# can-rs232.net
KiCad netlist of a schematic drawn in EAGLE
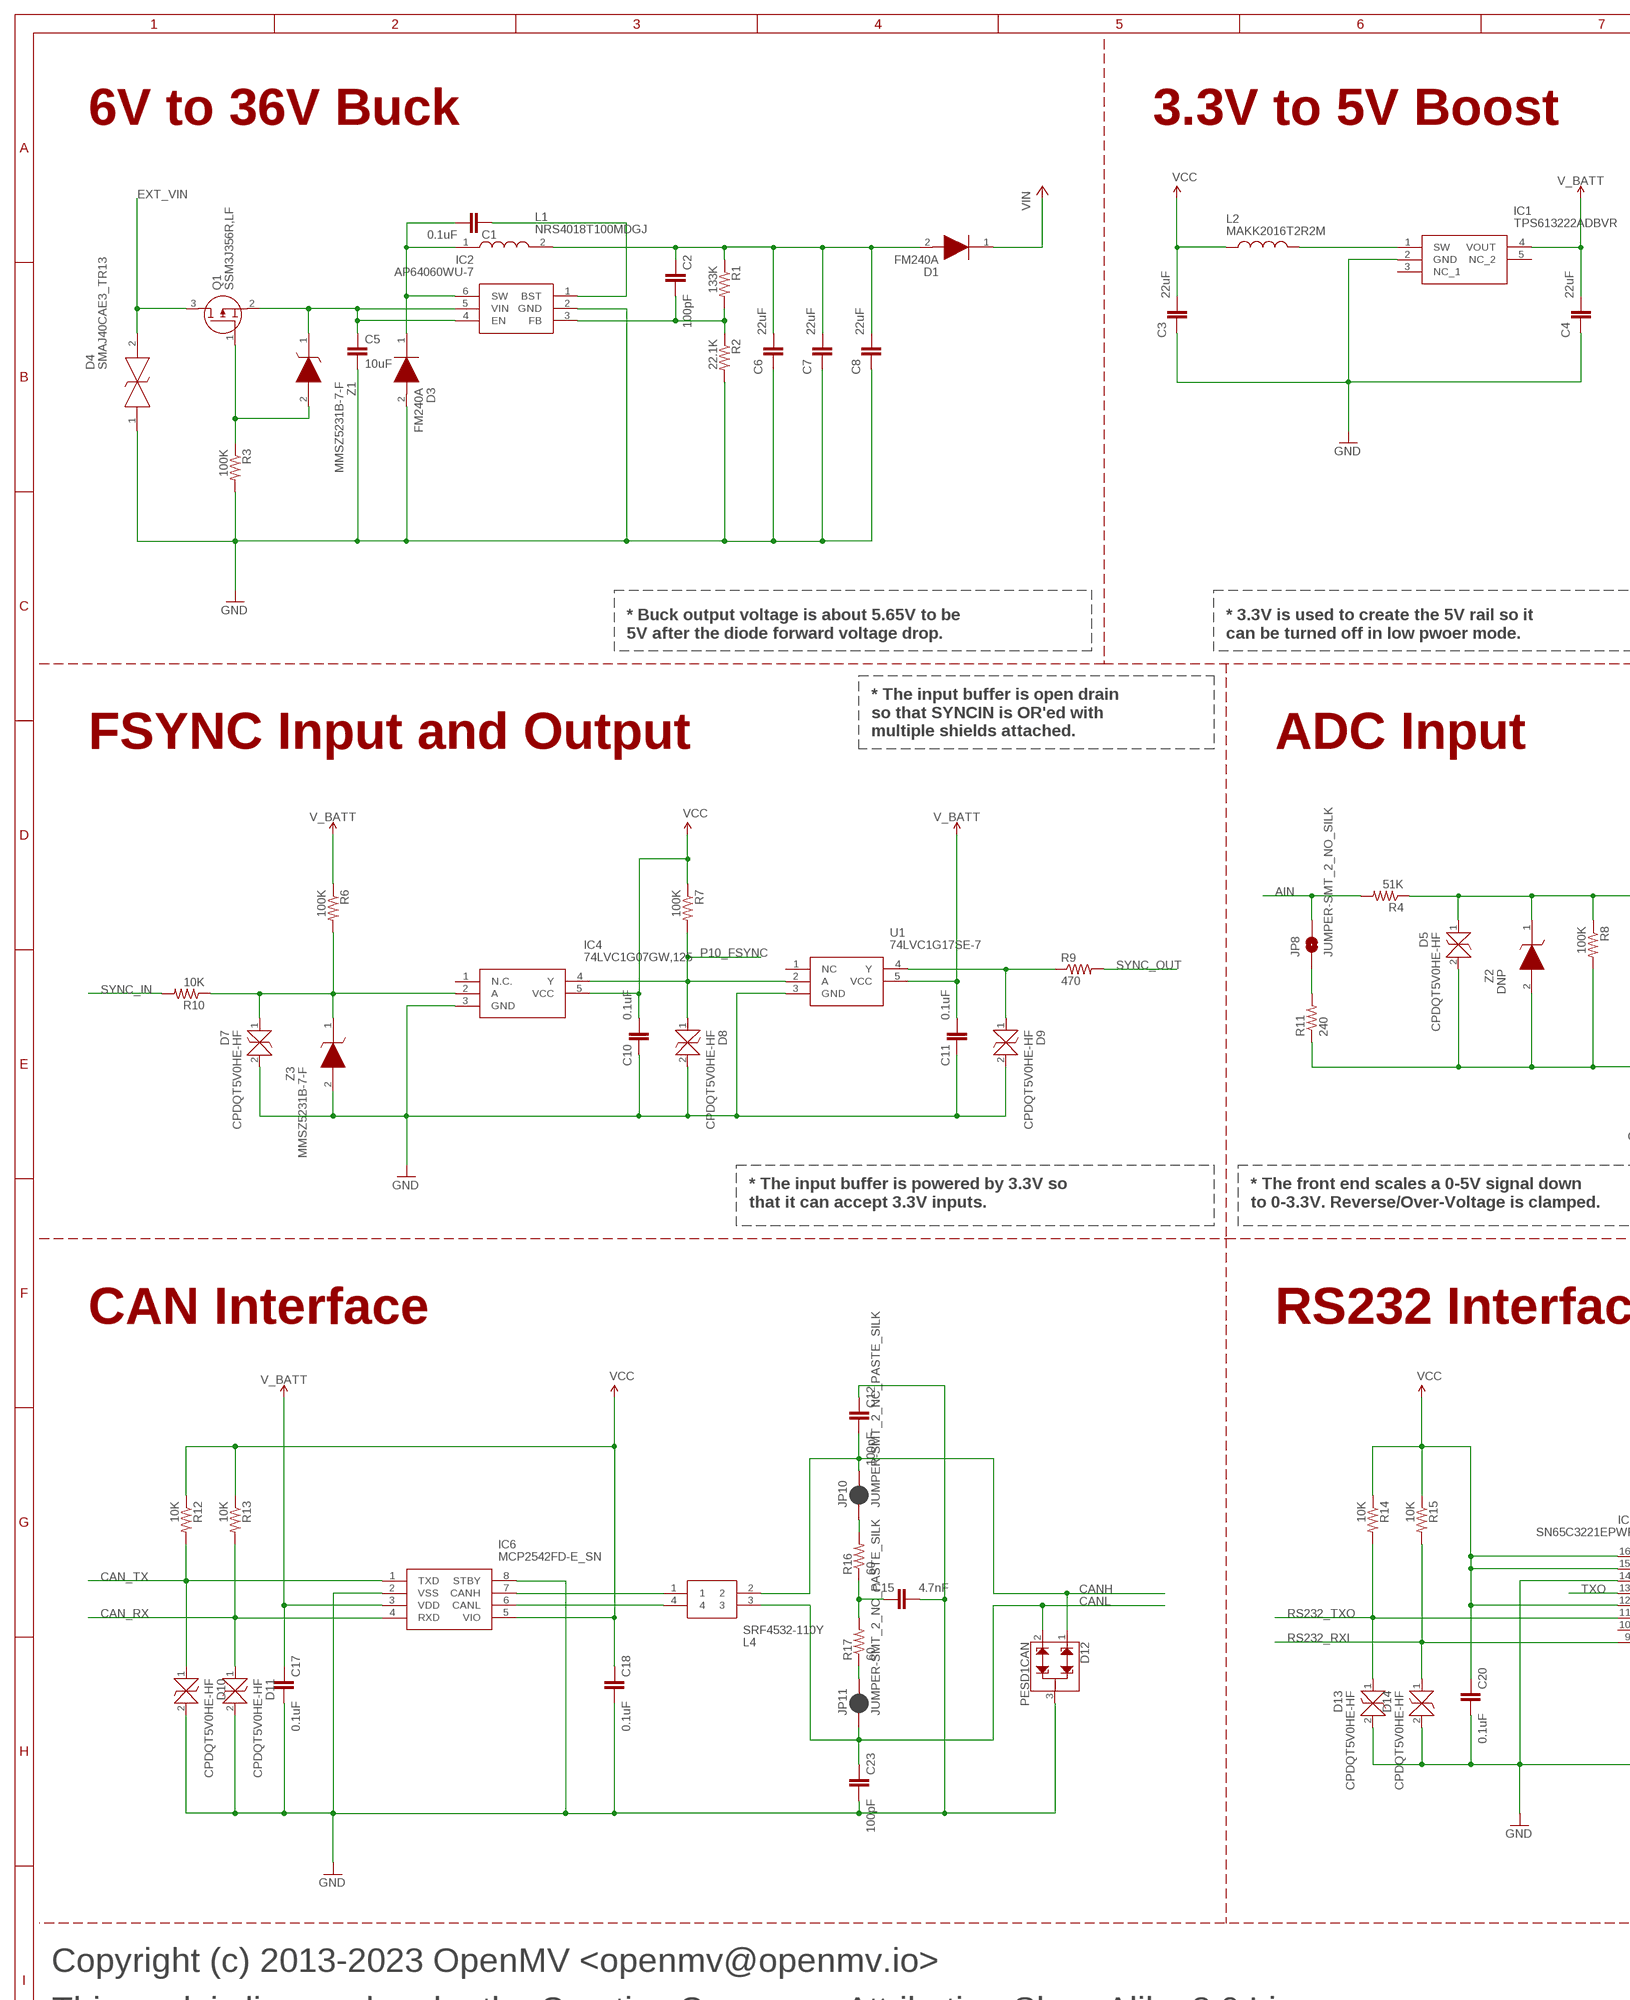
[diagram p0: schematic, sheet 1, part 1 of 2]
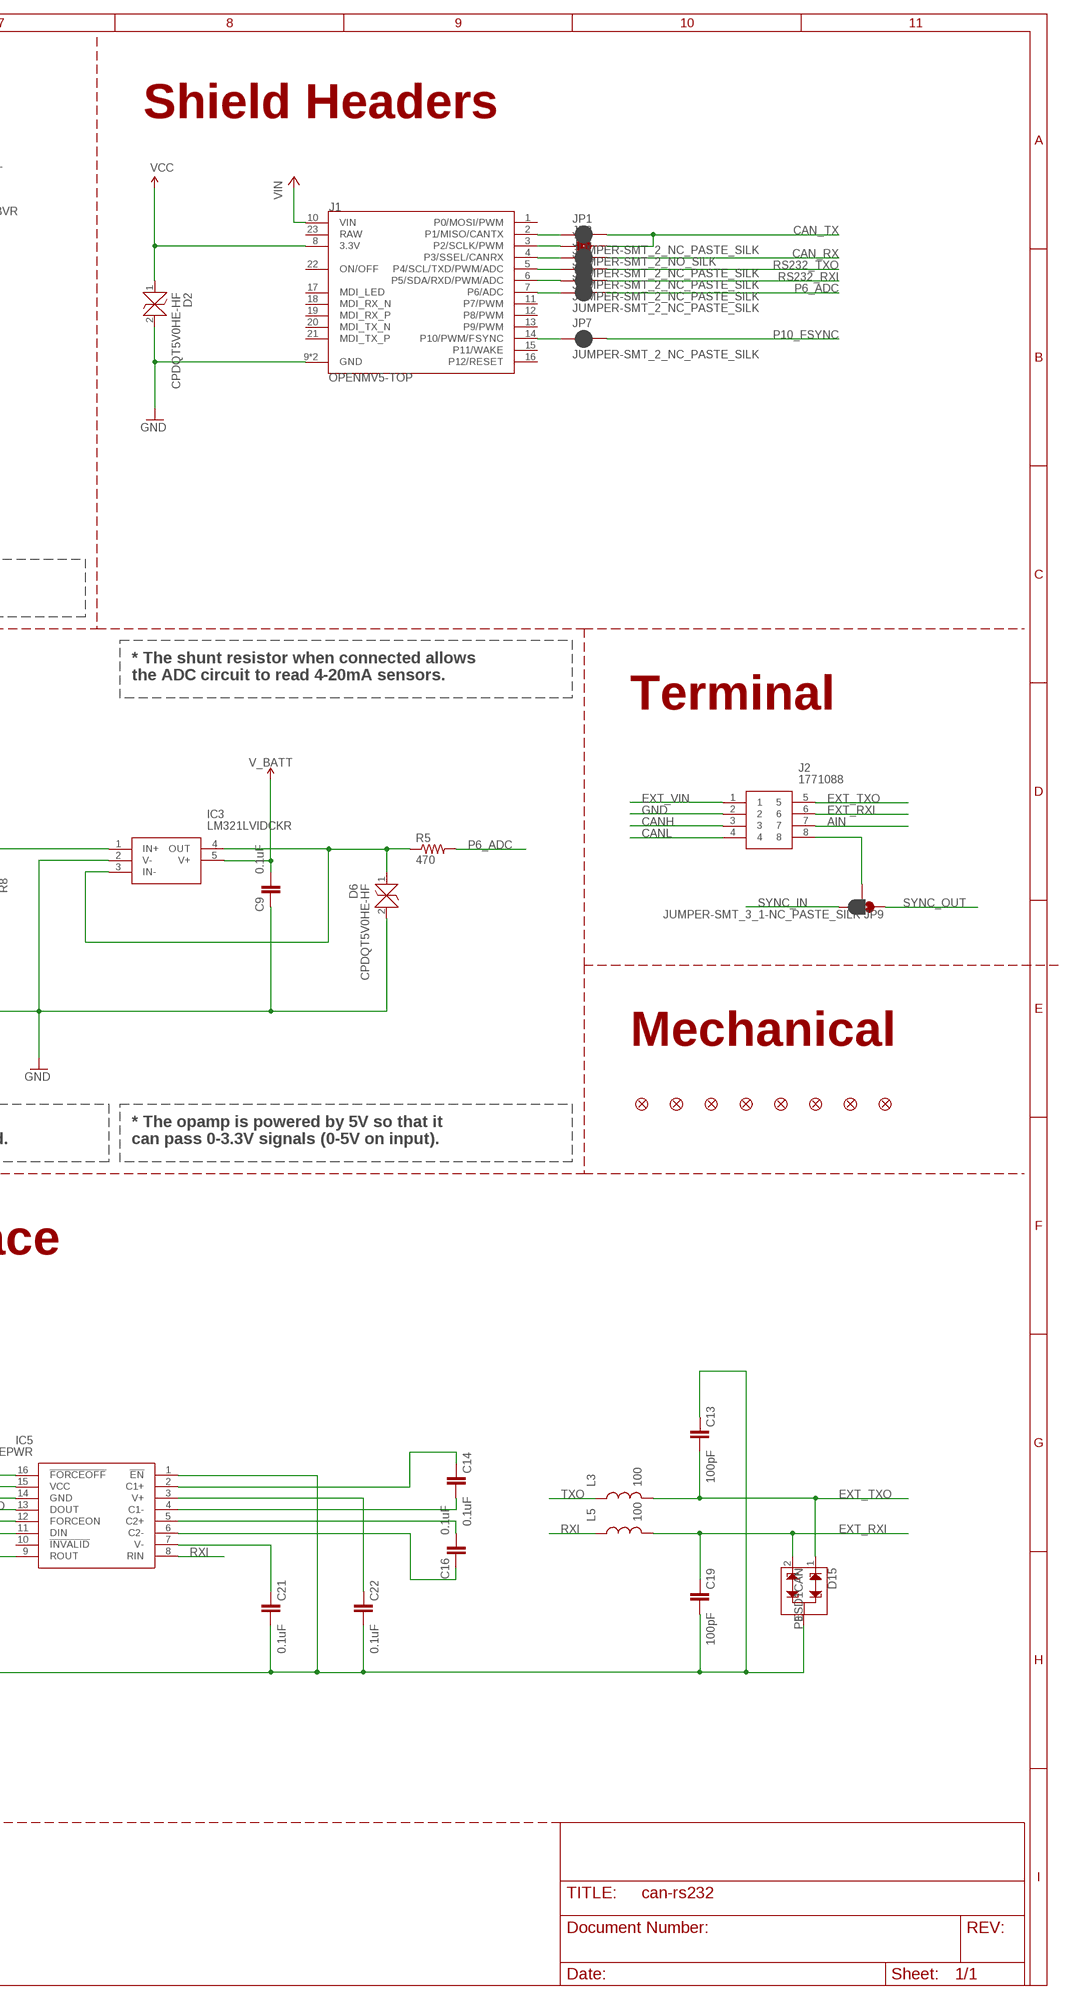
[diagram p1: schematic, sheet 1, part 2 of 2]

(export (version "E")
  (design (tool "Eeschema 10.0.6"))
  (components
    (comp (ref "C1")
      (value "0.1uF")
      (footprint "eagle-import:0402-CAP")
      (fields (field (name "MPN") "GRM155R71H104KE14D"))
      (libsource (lib "eagle-import") (part "CAP0402-CAP"))
    )
    (comp (ref "C2")
      (value "100pF")
      (footprint "eagle-import:0402-CAP")
      (fields (field (name "MPN") "CC0402JRNPO9BN101"))
      (libsource (lib "eagle-import") (part "CAP0402-CAP"))
    )
    (comp (ref "C3")
      (value "22uF")
      (footprint "eagle-import:0805")
      (fields (field (name "MPN") "CL21A226MQQNNNE"))
      (libsource (lib "eagle-import") (part "22UF-0805-6.3V-20%"))
    )
    (comp (ref "C4")
      (value "22uF")
      (footprint "eagle-import:0805")
      (fields (field (name "MPN") "CL21A226MQQNNNE"))
      (libsource (lib "eagle-import") (part "22UF-0805-6.3V-20%"))
    )
    (comp (ref "C5")
      (value "10uF")
      (footprint "eagle-import:C0805")
      (fields (field (name "MPN") "GRM21BR61H106KE43K"))
      (libsource (lib "eagle-import") (part "C-EUC0805"))
    )
    (comp (ref "C6")
      (value "22uF")
      (footprint "eagle-import:0805")
      (fields (field (name "MPN") "CL21A226MQQNNNE"))
      (libsource (lib "eagle-import") (part "22UF-0805-6.3V-20%"))
    )
    (comp (ref "C7")
      (value "22uF")
      (footprint "eagle-import:0805")
      (fields (field (name "MPN") "CL21A226MQQNNNE"))
      (libsource (lib "eagle-import") (part "22UF-0805-6.3V-20%"))
    )
    (comp (ref "C8")
      (value "22uF")
      (footprint "eagle-import:0805")
      (fields (field (name "MPN") "CL21A226MQQNNNE"))
      (libsource (lib "eagle-import") (part "22UF-0805-6.3V-20%"))
    )
    (comp (ref "C9")
      (value "0.1uF")
      (footprint "eagle-import:0402-CAP")
      (fields (field (name "MPN") "GRM155R71H104KE14D"))
      (libsource (lib "eagle-import") (part "CAP0402-CAP"))
    )
    (comp (ref "C10")
      (value "0.1uF")
      (footprint "eagle-import:0402-CAP")
      (fields (field (name "MPN") "GRM155R71H104KE14D"))
      (libsource (lib "eagle-import") (part "CAP0402-CAP"))
    )
    (comp (ref "C11")
      (value "0.1uF")
      (footprint "eagle-import:0402-CAP")
      (fields (field (name "MPN") "GRM155R71H104KE14D"))
      (libsource (lib "eagle-import") (part "CAP0402-CAP"))
    )
    (comp (ref "C12")
      (value "100pF")
      (footprint "eagle-import:0402-CAP")
      (fields (field (name "MPN") "CC0402JRNPO9BN101"))
      (libsource (lib "eagle-import") (part "CAP0402-CAP"))
    )
    (comp (ref "C13")
      (value "100pF")
      (footprint "eagle-import:0402-CAP")
      (fields (field (name "MPN") "CC0402JRNPO9BN101"))
      (libsource (lib "eagle-import") (part "CAP0402-CAP"))
    )
    (comp (ref "C14")
      (value "0.1uF")
      (footprint "eagle-import:0402-CAP")
      (fields (field (name "MPN") "GRM155R71H104KE14D"))
      (libsource (lib "eagle-import") (part "CAP0402-CAP"))
    )
    (comp (ref "C15")
      (value "4.7nF")
      (footprint "eagle-import:0402-CAP")
      (fields (field (name "MPN") "GRM155R71H472JA01D"))
      (libsource (lib "eagle-import") (part "CAP0402-CAP"))
    )
    (comp (ref "C16")
      (value "0.1uF")
      (footprint "eagle-import:0402-CAP")
      (fields (field (name "MPN") "GRM155R71H104KE14D"))
      (libsource (lib "eagle-import") (part "CAP0402-CAP"))
    )
    (comp (ref "C17")
      (value "0.1uF")
      (footprint "eagle-import:0402-CAP")
      (fields (field (name "MPN") "GRM155R71H104KE14D"))
      (libsource (lib "eagle-import") (part "CAP0402-CAP"))
    )
    (comp (ref "C18")
      (value "0.1uF")
      (footprint "eagle-import:0402-CAP")
      (fields (field (name "MPN") "GRM155R71H104KE14D"))
      (libsource (lib "eagle-import") (part "CAP0402-CAP"))
    )
    (comp (ref "C19")
      (value "100pF")
      (footprint "eagle-import:0402-CAP")
      (fields (field (name "MPN") "CC0402JRNPO9BN101"))
      (libsource (lib "eagle-import") (part "CAP0402-CAP"))
    )
    (comp (ref "C20")
      (value "0.1uF")
      (footprint "eagle-import:0402-CAP")
      (fields (field (name "MPN") "GRM155R71H104KE14D"))
      (libsource (lib "eagle-import") (part "CAP0402-CAP"))
    )
    (comp (ref "C21")
      (value "0.1uF")
      (footprint "eagle-import:0402-CAP")
      (fields (field (name "MPN") "GRM155R71H104KE14D"))
      (libsource (lib "eagle-import") (part "CAP0402-CAP"))
    )
    (comp (ref "C22")
      (value "0.1uF")
      (footprint "eagle-import:0402-CAP")
      (fields (field (name "MPN") "GRM155R71H104KE14D"))
      (libsource (lib "eagle-import") (part "CAP0402-CAP"))
    )
    (comp (ref "C23")
      (value "100pF")
      (footprint "eagle-import:0402-CAP")
      (fields (field (name "MPN") "CC0402JRNPO9BN101"))
      (libsource (lib "eagle-import") (part "CAP0402-CAP"))
    )
    (comp (ref "D1")
      (value "FM240A")
      (footprint "eagle-import:DIOM5025X231N")
      (fields (field (name "MOUSER_PART_NUMBER") "583-FM240A"))
      (libsource (lib "eagle-import") (part "FM240A"))
    )
    (comp (ref "D2")
      (value "CPDQT5V0HE-HF")
      (footprint "eagle-import:CPDQT5V0HEHF")
      (libsource (lib "eagle-import") (part "CPDQT5V0HE-HF"))
    )
    (comp (ref "D3")
      (value "FM240A")
      (footprint "eagle-import:DIOM5025X231N")
      (fields (field (name "MOUSER_PART_NUMBER") "583-FM240A"))
      (libsource (lib "eagle-import") (part "FM240A"))
    )
    (comp (ref "D4")
      (value "SMAJ40CAE3_TR13")
      (footprint "eagle-import:SMAJ40CAE3TR13")
      (fields
        (field (name "MANUFACTURER_PART_NUMBER") "SMAJ40CAe3/TR13")
        (field (name "MOUSER_PART_NUMBER") "494-SMAJ40CAE3/TR13")
      )
      (libsource (lib "eagle-import") (part "SMAJ40CAE3_TR13"))
    )
    (comp (ref "D5")
      (value "CPDQT5V0HE-HF")
      (footprint "eagle-import:CPDQT5V0HEHF")
      (libsource (lib "eagle-import") (part "CPDQT5V0HE-HF"))
    )
    (comp (ref "D6")
      (value "CPDQT5V0HE-HF")
      (footprint "eagle-import:CPDQT5V0HEHF")
      (libsource (lib "eagle-import") (part "CPDQT5V0HE-HF"))
    )
    (comp (ref "D7")
      (value "CPDQT5V0HE-HF")
      (footprint "eagle-import:CPDQT5V0HEHF")
      (libsource (lib "eagle-import") (part "CPDQT5V0HE-HF"))
    )
    (comp (ref "D8")
      (value "CPDQT5V0HE-HF")
      (footprint "eagle-import:CPDQT5V0HEHF")
      (libsource (lib "eagle-import") (part "CPDQT5V0HE-HF"))
    )
    (comp (ref "D9")
      (value "CPDQT5V0HE-HF")
      (footprint "eagle-import:CPDQT5V0HEHF")
      (libsource (lib "eagle-import") (part "CPDQT5V0HE-HF"))
    )
    (comp (ref "D10")
      (value "CPDQT5V0HE-HF")
      (footprint "eagle-import:CPDQT5V0HEHF")
      (libsource (lib "eagle-import") (part "CPDQT5V0HE-HF"))
    )
    (comp (ref "D11")
      (value "CPDQT5V0HE-HF")
      (footprint "eagle-import:CPDQT5V0HEHF")
      (libsource (lib "eagle-import") (part "CPDQT5V0HE-HF"))
    )
    (comp (ref "D12")
      (value "PESD1CAN")
      (footprint "eagle-import:SOT23-3")
      (fields (field (name "MPN") "VCAN36A2-03S-E3-08"))
      (libsource (lib "eagle-import") (part "PESD1CAN"))
    )
    (comp (ref "D13")
      (value "CPDQT5V0HE-HF")
      (footprint "eagle-import:CPDQT5V0HEHF")
      (libsource (lib "eagle-import") (part "CPDQT5V0HE-HF"))
    )
    (comp (ref "D14")
      (value "CPDQT5V0HE-HF")
      (footprint "eagle-import:CPDQT5V0HEHF")
      (libsource (lib "eagle-import") (part "CPDQT5V0HE-HF"))
    )
    (comp (ref "D15")
      (value "PESD1CAN")
      (footprint "eagle-import:SOT23-3")
      (fields (field (name "MPN") "VCAN36A2-03S-E3-08"))
      (libsource (lib "eagle-import") (part "PESD1CAN"))
    )
    (comp (ref "FD1")
      (value "FIDUCIAL1X2")
      (footprint "eagle-import:FIDUCIAL-1X2")
      (libsource (lib "eagle-import") (part "FIDUCIAL1X2"))
    )
    (comp (ref "FD2")
      (value "FIDUCIAL1X2")
      (footprint "eagle-import:FIDUCIAL-1X2")
      (libsource (lib "eagle-import") (part "FIDUCIAL1X2"))
    )
    (comp (ref "FD3")
      (value "FIDUCIAL1X2")
      (footprint "eagle-import:FIDUCIAL-1X2")
      (libsource (lib "eagle-import") (part "FIDUCIAL1X2"))
    )
    (comp (ref "FD4")
      (value "FIDUCIAL1X2")
      (footprint "eagle-import:FIDUCIAL-1X2")
      (libsource (lib "eagle-import") (part "FIDUCIAL1X2"))
    )
    (comp (ref "FD5")
      (value "FIDUCIAL1X2")
      (footprint "eagle-import:FIDUCIAL-1X2")
      (libsource (lib "eagle-import") (part "FIDUCIAL1X2"))
    )
    (comp (ref "FD6")
      (value "FIDUCIAL1X2")
      (footprint "eagle-import:FIDUCIAL-1X2")
      (libsource (lib "eagle-import") (part "FIDUCIAL1X2"))
    )
    (comp (ref "FD7")
      (value "FIDUCIAL1X2")
      (footprint "eagle-import:FIDUCIAL-1X2")
      (libsource (lib "eagle-import") (part "FIDUCIAL1X2"))
    )
    (comp (ref "FD8")
      (value "FIDUCIAL1X2")
      (footprint "eagle-import:FIDUCIAL-1X2")
      (libsource (lib "eagle-import") (part "FIDUCIAL1X2"))
    )
    (comp (ref "IC1")
      (value "TPS613222ADBVR")
      (footprint "eagle-import:SOT95P280X145-5N")
      (fields (field (name "MOUSER_PART_NUMBER") "595-TPS613222ADBVR"))
      (libsource (lib "eagle-import") (part "TPS613222ADBVR"))
    )
    (comp (ref "IC2")
      (value "AP64060WU-7")
      (footprint "eagle-import:SOT95P280X100-6N")
      (fields (field (name "MOUSER_PART_NUMBER") "621-AP64060WU-7"))
      (libsource (lib "eagle-import") (part "AP64060WU-7"))
    )
    (comp (ref "IC3")
      (value "LM321LVIDCKR")
      (footprint "eagle-import:SOT65P210X110-5N")
      (fields (field (name "MOUSER_PART_NUMBER") "595-LM321LVIDCKR"))
      (libsource (lib "eagle-import") (part "LM321LVIDCKR"))
    )
    (comp (ref "IC4")
      (value "74LVC1G07GW,125")
      (footprint "eagle-import:SOT65P212X110-5N")
      (fields (field (name "MOUSER_PART_NUMBER") "771-74LVC1G07GW-G"))
      (libsource (lib "eagle-import") (part "74LVC1G07GW,125"))
    )
    (comp (ref "IC5")
      (value "SN65C3221EPWR")
      (footprint "eagle-import:SOP65P640X120-16N")
      (fields (field (name "MOUSER_PART_NUMBER") "595-SN65C3221EPWR"))
      (libsource (lib "eagle-import") (part "SN65C3221EPWR"))
    )
    (comp (ref "IC6")
      (value "MCP2542FD-E_SN")
      (footprint "eagle-import:SOIC127P600X175-8N")
      (fields
        (field (name "MANUFACTURER_PART_NUMBER") "MCP2542FD-E/SN")
        (field (name "MOUSER_PART_NUMBER") "579-MCP2542FD-E/SN")
      )
      (libsource (lib "eagle-import") (part "MCP2542FD-E_SN"))
    )
    (comp (ref "J1")
      (value "OPENMV5-TOP")
      (footprint "eagle-import:OPENMV5-TOP")
      (libsource (lib "eagle-import") (part "OPENMV5-TOP"))
    )
    (comp (ref "J2")
      (value "1771088")
      (footprint "eagle-import:1771088")
      (fields (field (name "MOUSER_PART_NUMBER") "651-1771088"))
      (libsource (lib "eagle-import") (part "1771088"))
    )
    (comp (ref "JP1")
      (value "JUMPER-SMT_2_NC_PASTE_SILK")
      (footprint "eagle-import:SMT-JUMPER_2_NC_PASTE_SILK")
      (libsource (lib "eagle-import") (part "JUMPER-SMT_2_NC_PASTE_SILK"))
    )
    (comp (ref "JP2")
      (value "JUMPER-SMT_2_NO_SILK")
      (footprint "eagle-import:SMT-JUMPER_2_NO_SILK")
      (libsource (lib "eagle-import") (part "JUMPER-SMT_2_NO_SILK"))
    )
    (comp (ref "JP3")
      (value "JUMPER-SMT_2_NC_PASTE_SILK")
      (footprint "eagle-import:SMT-JUMPER_2_NC_PASTE_SILK")
      (libsource (lib "eagle-import") (part "JUMPER-SMT_2_NC_PASTE_SILK"))
    )
    (comp (ref "JP4")
      (value "JUMPER-SMT_2_NC_PASTE_SILK")
      (footprint "eagle-import:SMT-JUMPER_2_NC_PASTE_SILK")
      (libsource (lib "eagle-import") (part "JUMPER-SMT_2_NC_PASTE_SILK"))
    )
    (comp (ref "JP5")
      (value "JUMPER-SMT_2_NC_PASTE_SILK")
      (footprint "eagle-import:SMT-JUMPER_2_NC_PASTE_SILK")
      (libsource (lib "eagle-import") (part "JUMPER-SMT_2_NC_PASTE_SILK"))
    )
    (comp (ref "JP6")
      (value "JUMPER-SMT_2_NC_PASTE_SILK")
      (footprint "eagle-import:SMT-JUMPER_2_NC_PASTE_SILK")
      (libsource (lib "eagle-import") (part "JUMPER-SMT_2_NC_PASTE_SILK"))
    )
    (comp (ref "JP7")
      (value "JUMPER-SMT_2_NC_PASTE_SILK")
      (footprint "eagle-import:SMT-JUMPER_2_NC_PASTE_SILK")
      (libsource (lib "eagle-import") (part "JUMPER-SMT_2_NC_PASTE_SILK"))
    )
    (comp (ref "JP8")
      (value "JUMPER-SMT_2_NO_SILK")
      (footprint "eagle-import:SMT-JUMPER_2_NO_SILK")
      (libsource (lib "eagle-import") (part "JUMPER-SMT_2_NO_SILK"))
    )
    (comp (ref "JP9")
      (value "JUMPER-SMT_3_1-NC_PASTE_SILK")
      (footprint "eagle-import:SMT-JUMPER_3_1-NC_PASTE_SILK")
      (libsource (lib "eagle-import") (part "JUMPER-SMT_3_1-NC_PASTE_SILK"))
    )
    (comp (ref "JP10")
      (value "JUMPER-SMT_2_NC_PASTE_SILK")
      (footprint "eagle-import:SMT-JUMPER_2_NC_PASTE_SILK")
      (libsource (lib "eagle-import") (part "JUMPER-SMT_2_NC_PASTE_SILK"))
    )
    (comp (ref "JP11")
      (value "JUMPER-SMT_2_NC_PASTE_SILK")
      (footprint "eagle-import:SMT-JUMPER_2_NC_PASTE_SILK")
      (libsource (lib "eagle-import") (part "JUMPER-SMT_2_NC_PASTE_SILK"))
    )
    (comp (ref "L1")
      (value "NRS4018T100MDGJ")
      (footprint "eagle-import:NRS4018T100MDGJ")
      (fields (field (name "MOUSER_PART_NUMBER") "963-NRS4018T100MDGJ"))
      (libsource (lib "eagle-import") (part "NRS4018T100MDGJ"))
    )
    (comp (ref "L2")
      (value "MAKK2016T2R2M")
      (footprint "eagle-import:INDC2016X100N")
      (fields (field (name "MF") "Taiyo Yuden"))
      (libsource (lib "eagle-import") (part "MAKK2016T2R2M"))
    )
    (comp (ref "L3")
      (value "100")
      (footprint "eagle-import:C0402")
      (fields (field (name "MPN") "MFBM1V1005-101-R"))
      (libsource (lib "eagle-import") (part "INDUCTOR0402"))
    )
    (comp (ref "L4")
      (value "SRF4532-110Y")
      (footprint "eagle-import:SRF4532101Y")
      (fields (field (name "MOUSER_PART_NUMBER") "652-SRF4532-110Y"))
      (libsource (lib "eagle-import") (part "SRF4532-110Y"))
    )
    (comp (ref "L5")
      (value "100")
      (footprint "eagle-import:C0402")
      (fields (field (name "MPN") "MFBM1V1005-101-R"))
      (libsource (lib "eagle-import") (part "INDUCTOR0402"))
    )
    (comp (ref "Q1")
      (value "SSM3J356R,LF")
      (footprint "eagle-import:SOTFL95P240X88-3N")
      (fields (field (name "MOUSER_PART_NUMBER") "757-SSM3J356RLF"))
      (libsource (lib "eagle-import") (part "SSM3J356R,LF"))
    )
    (comp (ref "R1")
      (value "133K")
      (footprint "eagle-import:0402-RES")
      (fields (field (name "MPN") "RC0402FR-07133KL"))
      (libsource (lib "eagle-import") (part "RESISTOR0402-RES"))
    )
    (comp (ref "R2")
      (value "22.1K")
      (footprint "eagle-import:0402-RES")
      (fields (field (name "MPN") "CR0402-FX-2212GLF"))
      (libsource (lib "eagle-import") (part "RESISTOR0402-RES"))
    )
    (comp (ref "R3")
      (value "100K")
      (footprint "eagle-import:0402-RES")
      (fields (field (name "MPN") "AC0402FR-07100KL"))
      (libsource (lib "eagle-import") (part "RESISTOR0402-RES"))
    )
    (comp (ref "R4")
      (value "51K")
      (footprint "eagle-import:0402-RES")
      (fields (field (name "MPN") "RC0402JR-0751KL"))
      (libsource (lib "eagle-import") (part "RESISTOR0402-RES"))
    )
    (comp (ref "R5")
      (value "470")
      (footprint "eagle-import:R0603")
      (fields (field (name "MPN") "CR0603-FX-4700ELF"))
      (libsource (lib "eagle-import") (part "R-US_R0603"))
    )
    (comp (ref "R6")
      (value "100K")
      (footprint "eagle-import:0402-RES")
      (fields (field (name "MPN") "AC0402FR-07100KL"))
      (libsource (lib "eagle-import") (part "RESISTOR0402-RES"))
    )
    (comp (ref "R7")
      (value "100K")
      (footprint "eagle-import:0402-RES")
      (fields (field (name "MPN") "AC0402FR-07100KL"))
      (libsource (lib "eagle-import") (part "RESISTOR0402-RES"))
    )
    (comp (ref "R8")
      (value "100K")
      (footprint "eagle-import:0402-RES")
      (fields (field (name "MPN") "AC0402FR-07100KL"))
      (libsource (lib "eagle-import") (part "RESISTOR0402-RES"))
    )
    (comp (ref "R9")
      (value "470")
      (footprint "eagle-import:R0603")
      (fields (field (name "MPN") "CR0603-FX-4700ELF"))
      (libsource (lib "eagle-import") (part "R-US_R0603"))
    )
    (comp (ref "R10")
      (value "10K")
      (footprint "eagle-import:0402-RES")
      (fields (field (name "MPN") "AC0402FR-1310KL"))
      (libsource (lib "eagle-import") (part "RESISTOR0402-RES"))
    )
    (comp (ref "R11")
      (value "240")
      (footprint "eagle-import:R0603")
      (fields (field (name "MPN") "RK73B1JTTD241J"))
      (libsource (lib "eagle-import") (part "R-US_R0603"))
    )
    (comp (ref "R12")
      (value "10K")
      (footprint "eagle-import:0402-RES")
      (fields (field (name "MPN") "AC0402FR-1310KL"))
      (libsource (lib "eagle-import") (part "RESISTOR0402-RES"))
    )
    (comp (ref "R13")
      (value "10K")
      (footprint "eagle-import:0402-RES")
      (fields (field (name "MPN") "AC0402FR-1310KL"))
      (libsource (lib "eagle-import") (part "RESISTOR0402-RES"))
    )
    (comp (ref "R14")
      (value "10K")
      (footprint "eagle-import:0402-RES")
      (fields (field (name "MPN") "AC0402FR-1310KL"))
      (libsource (lib "eagle-import") (part "RESISTOR0402-RES"))
    )
    (comp (ref "R15")
      (value "10K")
      (footprint "eagle-import:0402-RES")
      (fields (field (name "MPN") "AC0402FR-1310KL"))
      (libsource (lib "eagle-import") (part "RESISTOR0402-RES"))
    )
    (comp (ref "R16")
      (value "60")
      (footprint "eagle-import:R1206")
      (fields (field (name "MPN") "RC1206FR-0760R4L"))
      (libsource (lib "eagle-import") (part "R-US_R1206"))
    )
    (comp (ref "R17")
      (value "60")
      (footprint "eagle-import:R1206")
      (fields (field (name "MPN") "RC1206FR-0760R4L"))
      (libsource (lib "eagle-import") (part "R-US_R1206"))
    )
    (comp (ref "U1")
      (value "74LVC1G17SE-7")
      (footprint "eagle-import:SOT65P210X110-5N")
      (fields (field (name "MOUSER_PART_NUMBER") "621-74LVC1G17SE-7"))
      (libsource (lib "eagle-import") (part "74LVC1G17SE-7"))
    )
    (comp (ref "Z1")
      (value "MMSZ5231B-7-F")
      (footprint "eagle-import:SOD3716X145N")
      (fields (field (name "MOUSER_PART_NUMBER") "621-MMSZ5231B-F"))
      (libsource (lib "eagle-import") (part "MMSZ5231B-7-F"))
    )
    (comp (ref "Z2")
      (value "DNP")
      (footprint "eagle-import:SOD2512X110N")
      (fields
        (field (name "MANUFACTURER_PART_NUMBER") "MM3Z3V6T1G")
        (field (name "MOUSER_PART_NUMBER") "863-MM3Z3V6T1G")
      )
      (libsource (lib "eagle-import") (part "MM3Z3V6T1G"))
    )
    (comp (ref "Z3")
      (value "MMSZ5231B-7-F")
      (footprint "eagle-import:SOD3716X145N")
      (fields (field (name "MOUSER_PART_NUMBER") "621-MMSZ5231B-F"))
      (libsource (lib "eagle-import") (part "MMSZ5231B-7-F"))
    )
  )
  (nets
    (net (code "1") (name "/AIN") (class "Default")
      (node (ref "J2") (pin "7") (pinfunction "7_7") (pintype "bidirectional"))
      (node (ref "JP8") (pin "2") (pinfunction "2_2") (pintype "passive"))
      (node (ref "R4") (pin "2") (pinfunction "2_2") (pintype "passive"))
    )
    (net (code "2") (name "/CANH") (class "Default")
      (node (ref "C12") (pin "2") (pinfunction "2_2") (pintype "passive"))
      (node (ref "D12") (pin "1") (pinfunction "1_1") (pintype "bidirectional"))
      (node (ref "J2") (pin "3") (pinfunction "3_3") (pintype "bidirectional"))
      (node (ref "JP10") (pin "2") (pinfunction "2_2") (pintype "passive"))
      (node (ref "L4") (pin "2") (pinfunction "2_2") (pintype "bidirectional"))
    )
    (net (code "3") (name "/CANL") (class "Default")
      (node (ref "C23") (pin "1") (pinfunction "1_1") (pintype "passive"))
      (node (ref "D12") (pin "2") (pinfunction "2_2") (pintype "bidirectional"))
      (node (ref "J2") (pin "4") (pinfunction "4_4") (pintype "bidirectional"))
      (node (ref "JP11") (pin "1") (pinfunction "1_1") (pintype "passive"))
      (node (ref "L4") (pin "3") (pinfunction "3_3") (pintype "bidirectional"))
    )
    (net (code "4") (name "/CAN_RX") (class "Default")
      (node (ref "D11") (pin "1") (pinfunction "1_1") (pintype "bidirectional"))
      (node (ref "IC6") (pin "4") (pinfunction "RXD_4") (pintype "bidirectional"))
      (node (ref "JP3") (pin "2") (pinfunction "2_2") (pintype "passive"))
      (node (ref "R13") (pin "2") (pinfunction "2_2") (pintype "passive"))
    )
    (net (code "5") (name "/CAN_TX") (class "Default")
      (node (ref "D10") (pin "1") (pinfunction "1_1") (pintype "bidirectional"))
      (node (ref "IC6") (pin "1") (pinfunction "TXD_1") (pintype "bidirectional"))
      (node (ref "JP1") (pin "2") (pinfunction "2_2") (pintype "passive"))
      (node (ref "JP2") (pin "2") (pinfunction "2_2") (pintype "passive"))
      (node (ref "R12") (pin "2") (pinfunction "2_2") (pintype "passive"))
    )
    (net (code "6") (name "/EXT_RXI") (class "Default")
      (node (ref "C19") (pin "1") (pinfunction "1_1") (pintype "passive"))
      (node (ref "D15") (pin "2") (pinfunction "2_2") (pintype "bidirectional"))
      (node (ref "J2") (pin "6") (pinfunction "6_6") (pintype "bidirectional"))
      (node (ref "L5") (pin "2") (pinfunction "2_2") (pintype "passive"))
    )
    (net (code "7") (name "/EXT_TXO") (class "Default")
      (node (ref "C13") (pin "2") (pinfunction "2_2") (pintype "passive"))
      (node (ref "D15") (pin "1") (pinfunction "1_1") (pintype "bidirectional"))
      (node (ref "J2") (pin "5") (pinfunction "5_5") (pintype "bidirectional"))
      (node (ref "L3") (pin "2") (pinfunction "2_2") (pintype "passive"))
    )
    (net (code "8") (name "/EXT_VIN") (class "Default")
      (node (ref "D4") (pin "2") (pinfunction "2_2") (pintype "bidirectional"))
      (node (ref "J2") (pin "1") (pinfunction "1_1") (pintype "bidirectional"))
      (node (ref "Q1") (pin "3") (pinfunction "D_3") (pintype "bidirectional"))
    )
    (net (code "9") (name "/P6_ADC") (class "Default")
      (node (ref "JP6") (pin "2") (pinfunction "2_2") (pintype "passive"))
      (node (ref "R5") (pin "2") (pinfunction "2_2") (pintype "passive"))
    )
    (net (code "10") (name "/P10_FSYNC") (class "Default")
      (node (ref "D8") (pin "1") (pinfunction "1_1") (pintype "bidirectional"))
      (node (ref "IC4") (pin "4") (pinfunction "Y_4") (pintype "bidirectional"))
      (node (ref "JP7") (pin "2") (pinfunction "2_2") (pintype "passive"))
      (node (ref "R7") (pin "2") (pinfunction "2_2") (pintype "passive"))
      (node (ref "U1") (pin "2") (pinfunction "A_2") (pintype "bidirectional"))
    )
    (net (code "11") (name "/RAW") (class "Default")
      (node (ref "J1") (pin "23") (pinfunction "RAW_23") (pintype "power_in"))
    )
    (net (code "12") (name "/RS232_RXI") (class "Default")
      (node (ref "D14") (pin "1") (pinfunction "1_1") (pintype "bidirectional"))
      (node (ref "IC5") (pin "9") (pinfunction "ROUT_9") (pintype "bidirectional"))
      (node (ref "JP5") (pin "2") (pinfunction "2_2") (pintype "passive"))
      (node (ref "R15") (pin "2") (pinfunction "2_2") (pintype "passive"))
    )
    (net (code "13") (name "/RS232_TXO") (class "Default")
      (node (ref "D13") (pin "1") (pinfunction "1_1") (pintype "bidirectional"))
      (node (ref "IC5") (pin "11") (pinfunction "DIN_11") (pintype "bidirectional"))
      (node (ref "JP4") (pin "2") (pinfunction "2_2") (pintype "passive"))
      (node (ref "R14") (pin "2") (pinfunction "2_2") (pintype "passive"))
    )
    (net (code "14") (name "/RXI") (class "Default")
      (node (ref "IC5") (pin "8") (pinfunction "RIN_8") (pintype "bidirectional"))
      (node (ref "L5") (pin "1") (pinfunction "1_1") (pintype "passive"))
    )
    (net (code "15") (name "/SYNC_IN") (class "Default")
      (node (ref "JP9") (pin "3") (pinfunction "3_3") (pintype "passive"))
      (node (ref "R10") (pin "2") (pinfunction "2_2") (pintype "passive"))
    )
    (net (code "16") (name "/SYNC_OUT") (class "Default")
      (node (ref "JP9") (pin "1") (pinfunction "1_1") (pintype "passive"))
      (node (ref "R9") (pin "2") (pinfunction "2_2") (pintype "passive"))
    )
    (net (code "17") (name "/TXO") (class "Default")
      (node (ref "IC5") (pin "13") (pinfunction "DOUT_13") (pintype "bidirectional"))
      (node (ref "L3") (pin "1") (pinfunction "1_1") (pintype "passive"))
    )
    (net (code "18") (name "GND") (class "Default")
      (node (ref "C10") (pin "1") (pinfunction "1_1") (pintype "passive"))
      (node (ref "C11") (pin "1") (pinfunction "1_1") (pintype "passive"))
      (node (ref "C12") (pin "1") (pinfunction "1_1") (pintype "passive"))
      (node (ref "C13") (pin "1") (pinfunction "1_1") (pintype "passive"))
      (node (ref "C15") (pin "2") (pinfunction "2_2") (pintype "passive"))
      (node (ref "C17") (pin "2") (pinfunction "2_2") (pintype "passive"))
      (node (ref "C18") (pin "2") (pinfunction "2_2") (pintype "passive"))
      (node (ref "C19") (pin "2") (pinfunction "2_2") (pintype "passive"))
      (node (ref "C20") (pin "2") (pinfunction "2_2") (pintype "passive"))
      (node (ref "C21") (pin "2") (pinfunction "2_2") (pintype "passive"))
      (node (ref "C22") (pin "2") (pinfunction "2_2") (pintype "passive"))
      (node (ref "C23") (pin "2") (pinfunction "2_2") (pintype "passive"))
      (node (ref "C3") (pin "1") (pinfunction "1_1") (pintype "passive"))
      (node (ref "C4") (pin "1") (pinfunction "1_1") (pintype "passive"))
      (node (ref "C5") (pin "2") (pinfunction "2_2") (pintype "passive"))
      (node (ref "C6") (pin "1") (pinfunction "1_1") (pintype "passive"))
      (node (ref "C7") (pin "1") (pinfunction "1_1") (pintype "passive"))
      (node (ref "C8") (pin "1") (pinfunction "1_1") (pintype "passive"))
      (node (ref "C9") (pin "1") (pinfunction "1_1") (pintype "passive"))
      (node (ref "D10") (pin "2") (pinfunction "2_2") (pintype "bidirectional"))
      (node (ref "D11") (pin "2") (pinfunction "2_2") (pintype "bidirectional"))
      (node (ref "D12") (pin "3") (pinfunction "3_3") (pintype "bidirectional"))
      (node (ref "D13") (pin "2") (pinfunction "2_2") (pintype "bidirectional"))
      (node (ref "D14") (pin "2") (pinfunction "2_2") (pintype "bidirectional"))
      (node (ref "D15") (pin "3") (pinfunction "3_3") (pintype "bidirectional"))
      (node (ref "D2") (pin "2") (pinfunction "2_2") (pintype "bidirectional"))
      (node (ref "D3") (pin "2") (pinfunction "A_2") (pintype "bidirectional"))
      (node (ref "D4") (pin "1") (pinfunction "1_1") (pintype "bidirectional"))
      (node (ref "D5") (pin "2") (pinfunction "2_2") (pintype "bidirectional"))
      (node (ref "D6") (pin "2") (pinfunction "2_2") (pintype "bidirectional"))
      (node (ref "D7") (pin "2") (pinfunction "2_2") (pintype "bidirectional"))
      (node (ref "D8") (pin "2") (pinfunction "2_2") (pintype "bidirectional"))
      (node (ref "D9") (pin "2") (pinfunction "2_2") (pintype "bidirectional"))
      (node (ref "IC1") (pin "2") (pinfunction "GND_2") (pintype "bidirectional"))
      (node (ref "IC2") (pin "2") (pinfunction "GND_2") (pintype "bidirectional"))
      (node (ref "IC3") (pin "2") (pinfunction "V-_2") (pintype "input"))
      (node (ref "IC4") (pin "3") (pinfunction "GND_3") (pintype "bidirectional"))
      (node (ref "IC5") (pin "1") (pinfunction "~{EN}_1") (pintype "bidirectional"))
      (node (ref "IC5") (pin "14") (pinfunction "GND_14") (pintype "bidirectional"))
      (node (ref "IC6") (pin "2") (pinfunction "VSS_2") (pintype "bidirectional"))
      (node (ref "IC6") (pin "8") (pinfunction "STBY_8") (pintype "bidirectional"))
      (node (ref "J1") (pin "24") (pinfunction "GND_24") (pintype "power_in"))
      (node (ref "J1") (pin "9") (pinfunction "GND_9") (pintype "power_in"))
      (node (ref "J2") (pin "2") (pinfunction "2_2") (pintype "bidirectional"))
      (node (ref "R11") (pin "1") (pinfunction "1_1") (pintype "passive"))
      (node (ref "R2") (pin "2") (pinfunction "2_2") (pintype "passive"))
      (node (ref "R3") (pin "2") (pinfunction "2_2") (pintype "passive"))
      (node (ref "R8") (pin "2") (pinfunction "2_2") (pintype "passive"))
      (node (ref "U1") (pin "3") (pinfunction "GND_3") (pintype "bidirectional"))
      (node (ref "Z2") (pin "2") (pinfunction "A_2") (pintype "bidirectional"))
      (node (ref "Z3") (pin "2") (pinfunction "A_2") (pintype "bidirectional"))
    )
    (net (code "19") (name "Net-(C15-Pad1)") (class "Default")
      (node (ref "C15") (pin "1") (pinfunction "1_1") (pintype "passive"))
      (node (ref "R16") (pin "1") (pinfunction "1_1") (pintype "passive"))
      (node (ref "R17") (pin "2") (pinfunction "2_2") (pintype "passive"))
    )
    (net (code "20") (name "Net-(D1-A)") (class "Default")
      (node (ref "C2") (pin "1") (pinfunction "1_1") (pintype "passive"))
      (node (ref "C6") (pin "2") (pinfunction "2_2") (pintype "passive"))
      (node (ref "C7") (pin "2") (pinfunction "2_2") (pintype "passive"))
      (node (ref "C8") (pin "2") (pinfunction "2_2") (pintype "passive"))
      (node (ref "D1") (pin "2") (pinfunction "A_2") (pintype "bidirectional"))
      (node (ref "L1") (pin "2") (pinfunction "2_2") (pintype "bidirectional"))
      (node (ref "R1") (pin "1") (pinfunction "1_1") (pintype "passive"))
    )
    (net (code "21") (name "Net-(D3-K)") (class "Default")
      (node (ref "C1") (pin "2") (pinfunction "2_2") (pintype "passive"))
      (node (ref "D3") (pin "1") (pinfunction "K_1") (pintype "bidirectional"))
      (node (ref "IC2") (pin "6") (pinfunction "SW_6") (pintype "bidirectional"))
      (node (ref "L1") (pin "1") (pinfunction "1_1") (pintype "bidirectional"))
    )
    (net (code "22") (name "Net-(IC1-SW)") (class "Default")
      (node (ref "IC1") (pin "1") (pinfunction "SW_1") (pintype "bidirectional"))
      (node (ref "L2") (pin "2") (pinfunction "2_2") (pintype "passive"))
    )
    (net (code "23") (name "Net-(IC2-BST)") (class "Default")
      (node (ref "C1") (pin "1") (pinfunction "1_1") (pintype "passive"))
      (node (ref "IC2") (pin "1") (pinfunction "BST_1") (pintype "bidirectional"))
    )
    (net (code "24") (name "Net-(IC2-EN)") (class "Default")
      (node (ref "C5") (pin "1") (pinfunction "1_1") (pintype "passive"))
      (node (ref "IC2") (pin "4") (pinfunction "EN_4") (pintype "bidirectional"))
      (node (ref "IC2") (pin "5") (pinfunction "VIN_5") (pintype "bidirectional"))
      (node (ref "Q1") (pin "2") (pinfunction "S_2") (pintype "bidirectional"))
      (node (ref "Z1") (pin "1") (pinfunction "K_1") (pintype "bidirectional"))
    )
    (net (code "25") (name "Net-(IC2-FB)") (class "Default")
      (node (ref "C2") (pin "2") (pinfunction "2_2") (pintype "passive"))
      (node (ref "IC2") (pin "3") (pinfunction "FB_3") (pintype "bidirectional"))
      (node (ref "R1") (pin "2") (pinfunction "2_2") (pintype "passive"))
      (node (ref "R2") (pin "1") (pinfunction "1_1") (pintype "passive"))
    )
    (net (code "26") (name "Net-(IC3-IN+)") (class "Default")
      (node (ref "D5") (pin "1") (pinfunction "1_1") (pintype "bidirectional"))
      (node (ref "IC3") (pin "1") (pinfunction "IN+_1") (pintype "input"))
      (node (ref "R4") (pin "1") (pinfunction "1_1") (pintype "passive"))
      (node (ref "R8") (pin "1") (pinfunction "1_1") (pintype "passive"))
      (node (ref "Z2") (pin "1") (pinfunction "K_1") (pintype "bidirectional"))
    )
    (net (code "27") (name "Net-(IC3-IN-)") (class "Default")
      (node (ref "D6") (pin "1") (pinfunction "1_1") (pintype "bidirectional"))
      (node (ref "IC3") (pin "3") (pinfunction "IN-_3") (pintype "input"))
      (node (ref "IC3") (pin "4") (pinfunction "OUT_4") (pintype "output"))
      (node (ref "R5") (pin "1") (pinfunction "1_1") (pintype "passive"))
    )
    (net (code "28") (name "Net-(IC4-A)") (class "Default")
      (node (ref "D7") (pin "1") (pinfunction "1_1") (pintype "bidirectional"))
      (node (ref "IC4") (pin "2") (pinfunction "A_2") (pintype "bidirectional"))
      (node (ref "R10") (pin "1") (pinfunction "1_1") (pintype "passive"))
      (node (ref "R6") (pin "2") (pinfunction "2_2") (pintype "passive"))
      (node (ref "Z3") (pin "1") (pinfunction "K_1") (pintype "bidirectional"))
    )
    (net (code "29") (name "Net-(IC5-C1+)") (class "Default")
      (node (ref "C14") (pin "1") (pinfunction "1_1") (pintype "passive"))
      (node (ref "IC5") (pin "2") (pinfunction "C1+_2") (pintype "bidirectional"))
    )
    (net (code "30") (name "Net-(IC5-C1-)") (class "Default")
      (node (ref "C14") (pin "2") (pinfunction "2_2") (pintype "passive"))
      (node (ref "IC5") (pin "4") (pinfunction "C1-_4") (pintype "bidirectional"))
    )
    (net (code "31") (name "Net-(IC5-C2+)") (class "Default")
      (node (ref "C16") (pin "2") (pinfunction "2_2") (pintype "passive"))
      (node (ref "IC5") (pin "5") (pinfunction "C2+_5") (pintype "bidirectional"))
    )
    (net (code "32") (name "Net-(IC5-C2-)") (class "Default")
      (node (ref "C16") (pin "1") (pinfunction "1_1") (pintype "passive"))
      (node (ref "IC5") (pin "6") (pinfunction "C2-_6") (pintype "bidirectional"))
    )
    (net (code "33") (name "Net-(IC5-V+)") (class "Default")
      (node (ref "C22") (pin "1") (pinfunction "1_1") (pintype "passive"))
      (node (ref "IC5") (pin "3") (pinfunction "V+_3") (pintype "bidirectional"))
    )
    (net (code "34") (name "Net-(IC5-V-)") (class "Default")
      (node (ref "C21") (pin "1") (pinfunction "1_1") (pintype "passive"))
      (node (ref "IC5") (pin "7") (pinfunction "V-_7") (pintype "bidirectional"))
    )
    (net (code "35") (name "Net-(IC6-CANH)") (class "Default")
      (node (ref "IC6") (pin "7") (pinfunction "CANH_7") (pintype "bidirectional"))
      (node (ref "L4") (pin "1") (pinfunction "1_1") (pintype "bidirectional"))
    )
    (net (code "36") (name "Net-(IC6-CANL)") (class "Default")
      (node (ref "IC6") (pin "6") (pinfunction "CANL_6") (pintype "bidirectional"))
      (node (ref "L4") (pin "4") (pinfunction "4_4") (pintype "bidirectional"))
    )
    (net (code "37") (name "Net-(J1-P1{slash}MISO{slash}CANTX)") (class "Default")
      (node (ref "J1") (pin "2") (pinfunction "P1/MISO/CANTX_2") (pintype "bidirectional"))
      (node (ref "JP1") (pin "1") (pinfunction "1_1") (pintype "passive"))
    )
    (net (code "38") (name "Net-(J1-P2{slash}SCLK{slash}PWM)") (class "Default")
      (node (ref "J1") (pin "3") (pinfunction "P2/SCLK/PWM_3") (pintype "bidirectional"))
      (node (ref "JP2") (pin "1") (pinfunction "1_1") (pintype "passive"))
    )
    (net (code "39") (name "Net-(J1-P3{slash}SSEL{slash}CANRX)") (class "Default")
      (node (ref "J1") (pin "4") (pinfunction "P3/SSEL/CANRX_4") (pintype "bidirectional"))
      (node (ref "JP3") (pin "1") (pinfunction "1_1") (pintype "passive"))
    )
    (net (code "40") (name "Net-(J1-P4{slash}SCL{slash}TXD{slash}PWM{slash}ADC)") (class "Default")
      (node (ref "J1") (pin "5") (pinfunction "P4/SCL/TXD/PWM/ADC_5") (pintype "bidirectional"))
      (node (ref "JP4") (pin "1") (pinfunction "1_1") (pintype "passive"))
    )
    (net (code "41") (name "Net-(J1-P5{slash}SDA{slash}RXD{slash}PWM{slash}ADC)") (class "Default")
      (node (ref "J1") (pin "6") (pinfunction "P5/SDA/RXD/PWM/ADC_6") (pintype "bidirectional"))
      (node (ref "JP5") (pin "1") (pinfunction "1_1") (pintype "passive"))
    )
    (net (code "42") (name "Net-(J1-P6{slash}ADC)") (class "Default")
      (node (ref "J1") (pin "7") (pinfunction "P6/ADC_7") (pintype "bidirectional"))
      (node (ref "JP6") (pin "1") (pinfunction "1_1") (pintype "passive"))
    )
    (net (code "43") (name "Net-(J1-P10{slash}PWM{slash}FSYNC)") (class "Default")
      (node (ref "J1") (pin "14") (pinfunction "P10/PWM/FSYNC_14") (pintype "bidirectional"))
      (node (ref "JP7") (pin "1") (pinfunction "1_1") (pintype "passive"))
    )
    (net (code "44") (name "Net-(J2-Pad8)") (class "Default")
      (node (ref "J2") (pin "8") (pinfunction "8_8") (pintype "bidirectional"))
      (node (ref "JP9") (pin "2") (pinfunction "2_2") (pintype "passive"))
    )
    (net (code "45") (name "Net-(JP8-Pad1)") (class "Default")
      (node (ref "JP8") (pin "1") (pinfunction "1_1") (pintype "passive"))
      (node (ref "R11") (pin "2") (pinfunction "2_2") (pintype "passive"))
    )
    (net (code "46") (name "Net-(JP10-Pad1)") (class "Default")
      (node (ref "JP10") (pin "1") (pinfunction "1_1") (pintype "passive"))
      (node (ref "R16") (pin "2") (pinfunction "2_2") (pintype "passive"))
    )
    (net (code "47") (name "Net-(JP11-Pad2)") (class "Default")
      (node (ref "JP11") (pin "2") (pinfunction "2_2") (pintype "passive"))
      (node (ref "R17") (pin "1") (pinfunction "1_1") (pintype "passive"))
    )
    (net (code "48") (name "Net-(Q1-G)") (class "Default")
      (node (ref "Q1") (pin "1") (pinfunction "G_1") (pintype "bidirectional"))
      (node (ref "R3") (pin "1") (pinfunction "1_1") (pintype "passive"))
      (node (ref "Z1") (pin "2") (pinfunction "A_2") (pintype "bidirectional"))
    )
    (net (code "49") (name "Net-(U1-Y)") (class "Default")
      (node (ref "D9") (pin "1") (pinfunction "1_1") (pintype "bidirectional"))
      (node (ref "R9") (pin "1") (pinfunction "1_1") (pintype "passive"))
      (node (ref "U1") (pin "4") (pinfunction "Y_4") (pintype "bidirectional"))
    )
    (net (code "50") (name "VCC") (class "Default")
      (node (ref "C10") (pin "2") (pinfunction "2_2") (pintype "passive"))
      (node (ref "C18") (pin "1") (pinfunction "1_1") (pintype "passive"))
      (node (ref "C20") (pin "1") (pinfunction "1_1") (pintype "passive"))
      (node (ref "C3") (pin "2") (pinfunction "2_2") (pintype "passive"))
      (node (ref "D2") (pin "1") (pinfunction "1_1") (pintype "bidirectional"))
      (node (ref "IC4") (pin "5") (pinfunction "VCC_5") (pintype "bidirectional"))
      (node (ref "IC5") (pin "12") (pinfunction "FORCEON_12") (pintype "bidirectional"))
      (node (ref "IC5") (pin "15") (pinfunction "VCC_15") (pintype "bidirectional"))
      (node (ref "IC5") (pin "16") (pinfunction "~{FORCEOFF}_16") (pintype "bidirectional"))
      (node (ref "IC6") (pin "5") (pinfunction "VIO_5") (pintype "bidirectional"))
      (node (ref "J1") (pin "8") (pinfunction "3.3V_8") (pintype "power_in"))
      (node (ref "L2") (pin "1") (pinfunction "1_1") (pintype "passive"))
      (node (ref "R12") (pin "1") (pinfunction "1_1") (pintype "passive"))
      (node (ref "R13") (pin "1") (pinfunction "1_1") (pintype "passive"))
      (node (ref "R14") (pin "1") (pinfunction "1_1") (pintype "passive"))
      (node (ref "R15") (pin "1") (pinfunction "1_1") (pintype "passive"))
      (node (ref "R7") (pin "1") (pinfunction "1_1") (pintype "passive"))
    )
    (net (code "51") (name "VIN") (class "Default")
      (node (ref "D1") (pin "1") (pinfunction "K_1") (pintype "bidirectional"))
      (node (ref "J1") (pin "10") (pinfunction "VIN_10") (pintype "power_in"))
    )
    (net (code "52") (name "V_BATT") (class "Default")
      (node (ref "C11") (pin "2") (pinfunction "2_2") (pintype "passive"))
      (node (ref "C17") (pin "1") (pinfunction "1_1") (pintype "passive"))
      (node (ref "C4") (pin "2") (pinfunction "2_2") (pintype "passive"))
      (node (ref "C9") (pin "2") (pinfunction "2_2") (pintype "passive"))
      (node (ref "IC1") (pin "4") (pinfunction "VOUT_4") (pintype "bidirectional"))
      (node (ref "IC3") (pin "5") (pinfunction "V+_5") (pintype "input"))
      (node (ref "IC6") (pin "3") (pinfunction "VDD_3") (pintype "bidirectional"))
      (node (ref "R6") (pin "1") (pinfunction "1_1") (pintype "passive"))
      (node (ref "U1") (pin "5") (pinfunction "VCC_5") (pintype "bidirectional"))
    )
    (net (code "53") (name "unconnected-(IC1-NC_1-Pad3)") (class "Default")
      (node (ref "IC1") (pin "3") (pinfunction "NC_1_3") (pintype "bidirectional"))
    )
    (net (code "54") (name "unconnected-(IC1-NC_2-Pad5)") (class "Default")
      (node (ref "IC1") (pin "5") (pinfunction "NC_2_5") (pintype "bidirectional"))
    )
    (net (code "55") (name "unconnected-(IC4-N.C.-Pad1)") (class "Default")
      (node (ref "IC4") (pin "1") (pinfunction "N.C._1") (pintype "no_connect"))
    )
    (net (code "56") (name "unconnected-(IC5-~{INVALID}-Pad10)") (class "Default")
      (node (ref "IC5") (pin "10") (pinfunction "~{INVALID}_10") (pintype "bidirectional"))
    )
    (net (code "57") (name "unconnected-(J1-MDI_LED-Pad17)") (class "Default")
      (node (ref "J1") (pin "17") (pinfunction "MDI_LED_17") (pintype "bidirectional"))
    )
    (net (code "58") (name "unconnected-(J1-MDI_RX_N-Pad18)") (class "Default")
      (node (ref "J1") (pin "18") (pinfunction "MDI_RX_N_18") (pintype "bidirectional"))
    )
    (net (code "59") (name "unconnected-(J1-MDI_RX_P-Pad19)") (class "Default")
      (node (ref "J1") (pin "19") (pinfunction "MDI_RX_P_19") (pintype "bidirectional"))
    )
    (net (code "60") (name "unconnected-(J1-MDI_TX_N-Pad20)") (class "Default")
      (node (ref "J1") (pin "20") (pinfunction "MDI_TX_N_20") (pintype "bidirectional"))
    )
    (net (code "61") (name "unconnected-(J1-MDI_TX_P-Pad21)") (class "Default")
      (node (ref "J1") (pin "21") (pinfunction "MDI_TX_P_21") (pintype "bidirectional"))
    )
    (net (code "62") (name "unconnected-(J1-ON{slash}OFF-Pad22)") (class "Default")
      (node (ref "J1") (pin "22") (pinfunction "ON/OFF_22") (pintype "bidirectional"))
    )
    (net (code "63") (name "unconnected-(J1-P0{slash}MOSI{slash}PWM-Pad1)") (class "Default")
      (node (ref "J1") (pin "1") (pinfunction "P0/MOSI/PWM_1") (pintype "bidirectional"))
    )
    (net (code "64") (name "unconnected-(J1-P7{slash}PWM-Pad11)") (class "Default")
      (node (ref "J1") (pin "11") (pinfunction "P7/PWM_11") (pintype "bidirectional"))
    )
    (net (code "65") (name "unconnected-(J1-P8{slash}PWM-Pad12)") (class "Default")
      (node (ref "J1") (pin "12") (pinfunction "P8/PWM_12") (pintype "bidirectional"))
    )
    (net (code "66") (name "unconnected-(J1-P9{slash}PWM-Pad13)") (class "Default")
      (node (ref "J1") (pin "13") (pinfunction "P9/PWM_13") (pintype "bidirectional"))
    )
    (net (code "67") (name "unconnected-(J1-P11{slash}WAKE-Pad15)") (class "Default")
      (node (ref "J1") (pin "15") (pinfunction "P11/WAKE_15") (pintype "bidirectional"))
    )
    (net (code "68") (name "unconnected-(J1-P12{slash}RESET-Pad16)") (class "Default")
      (node (ref "J1") (pin "16") (pinfunction "P12/RESET_16") (pintype "bidirectional"))
    )
    (net (code "69") (name "unconnected-(U1-NC-Pad1)") (class "Default")
      (node (ref "U1") (pin "1") (pinfunction "NC_1") (pintype "no_connect"))
    )
  )
)
